# USBPROG_USBUART.net
KiCad netlist of a schematic drawn in Altium Designer
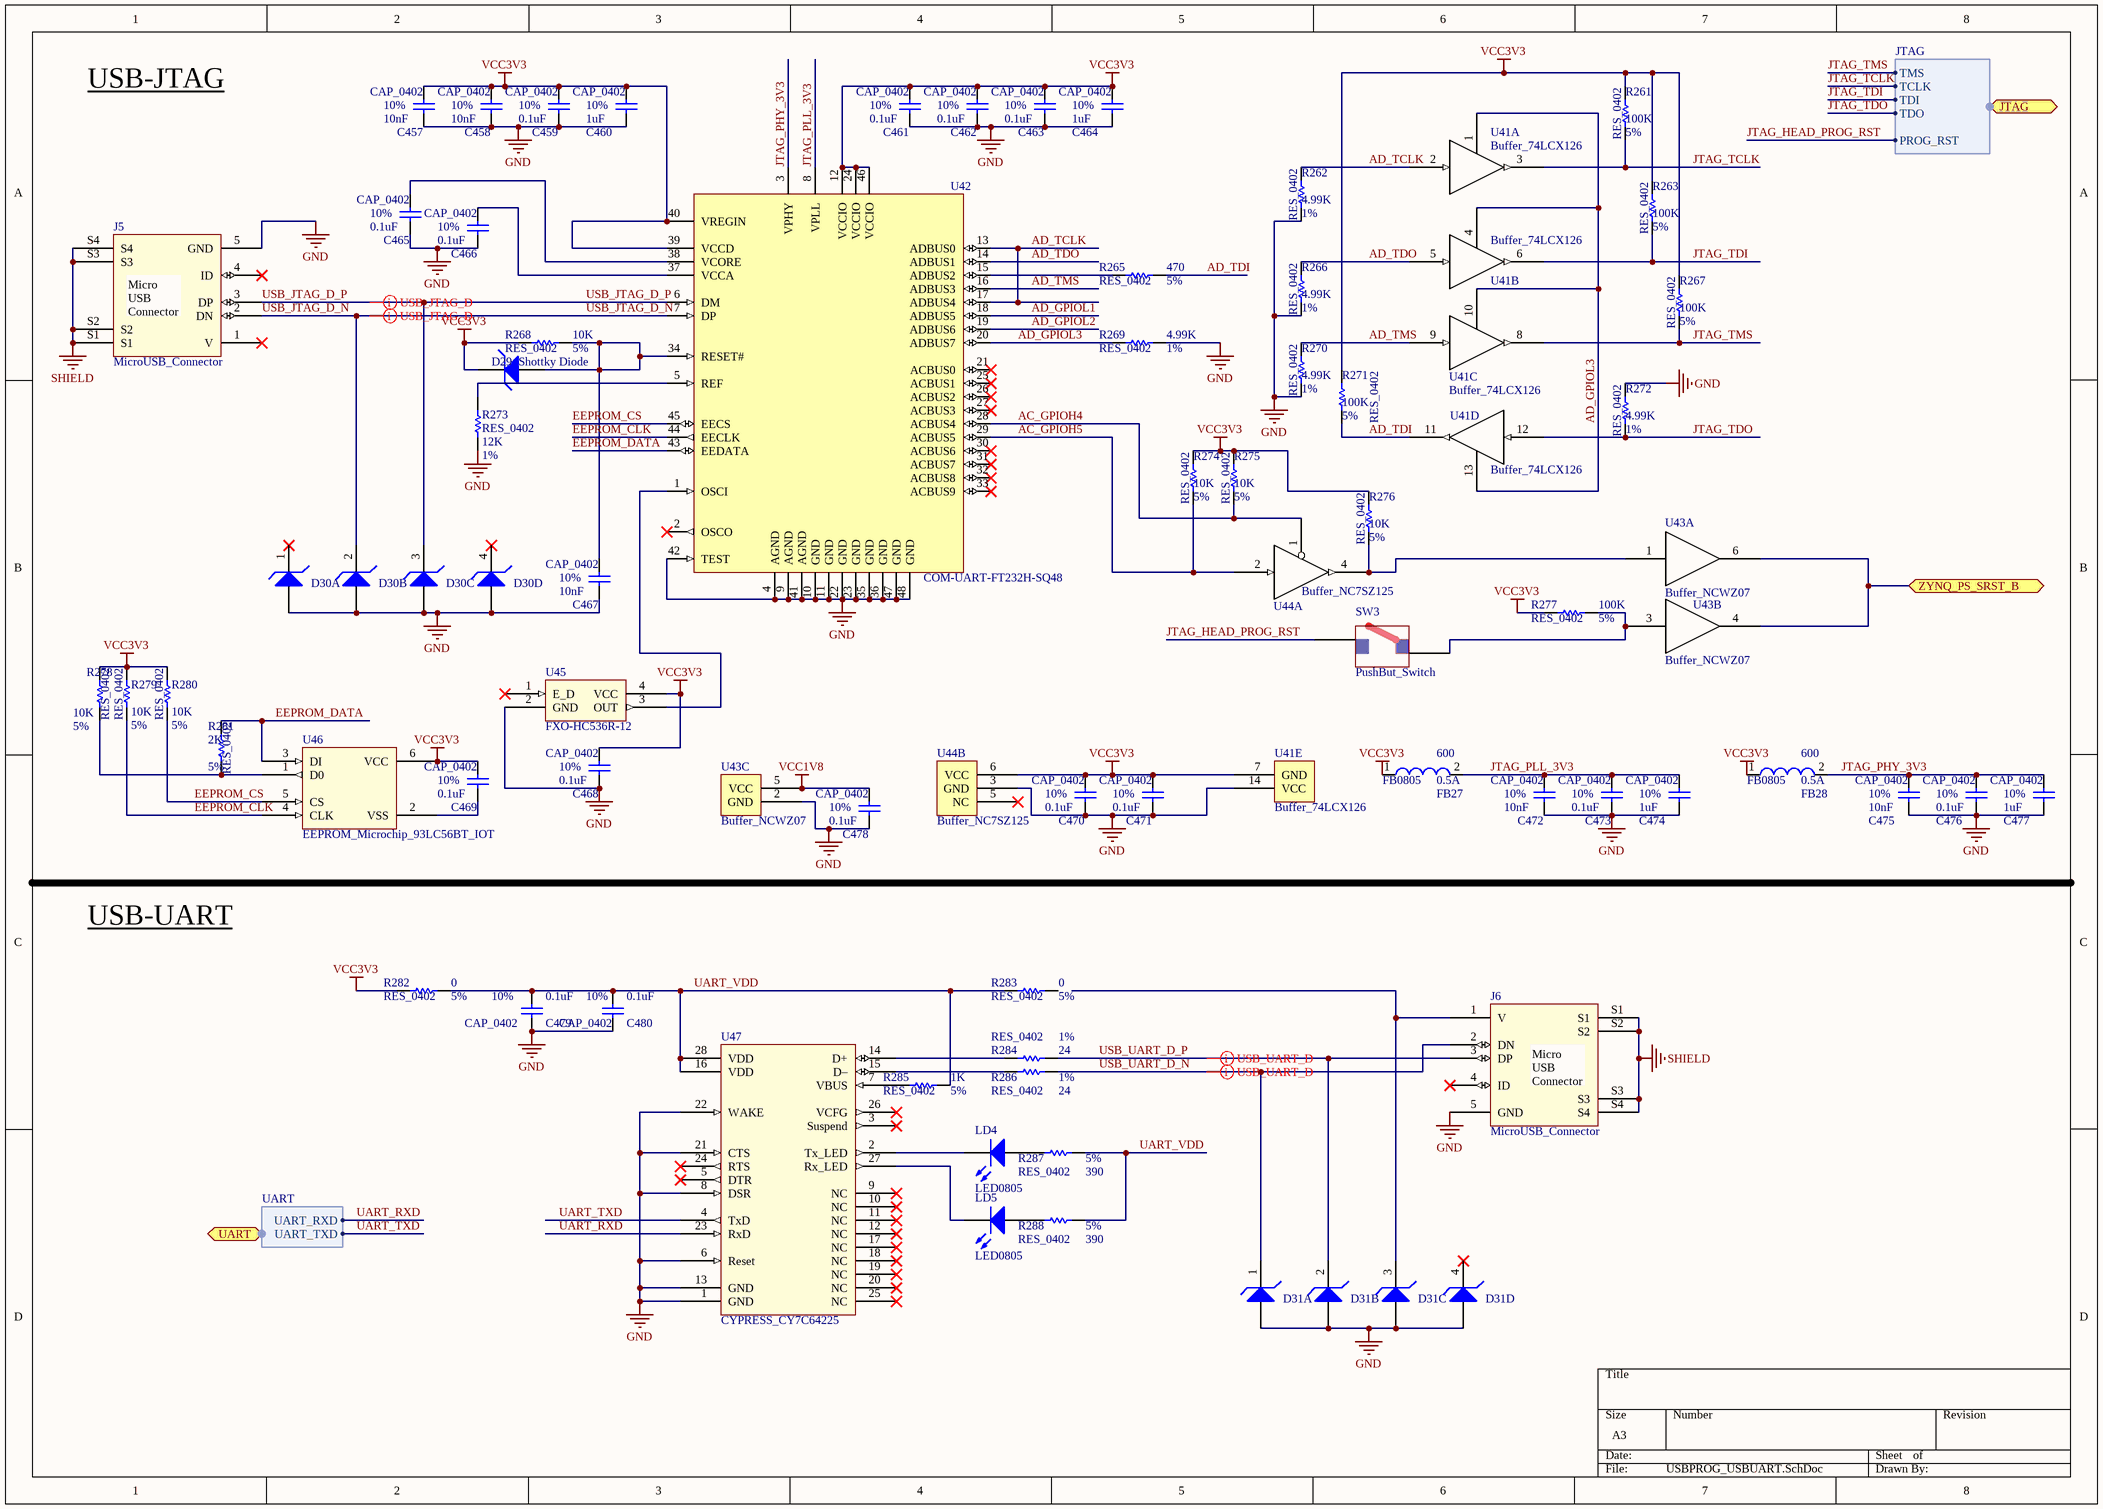
[diagram p0: USBPROG_USBUART.SchDoc]

(export (version "E")
  (design (tool "Eeschema 10.0.6"))
  (components
    (comp (ref "C457")
      (value "CAP_0402")
      (footprint "CAPC0402(1005)60_N:CAPC0402(1005)60_N")
      (description "10000pF, ceramic, 10% 6.3V X5R, 0402")
      (fields
        (field (name "ALTIUM_VALUE") "10nF")
        (field (name "TOLERANCE") "10%")
        (field (name "PART NUMBER") "GRM155R60J103KA01D")
        (field (name "MANUFACTURER") "Murata Electronics North America")
      )
      (libsource (lib "COMRAD_Database") (part "CAP_0402"))
    )
    (comp (ref "C458")
      (value "CAP_0402")
      (footprint "CAPC0402(1005)60_N:CAPC0402(1005)60_N")
      (description "10000pF, ceramic, 10% 6.3V X5R, 0402")
      (fields
        (field (name "ALTIUM_VALUE") "10nF")
        (field (name "TOLERANCE") "10%")
        (field (name "PART NUMBER") "GRM155R60J103KA01D")
        (field (name "MANUFACTURER") "Murata Electronics North America")
      )
      (libsource (lib "COMRAD_Database") (part "CAP_0402"))
    )
    (comp (ref "C459")
      (value "CAP_0402")
      (footprint "CAPC0402(1005)60_N:CAPC0402(1005)60_N")
      (description "0.1uf, ceramic, 10%, 6.3V, X5R, 0402")
      (fields
        (field (name "ALTIUM_VALUE") "0.1uF")
        (field (name "TOLERANCE") "10%")
        (field (name "PART NUMBER") "C1005X5R0J104K")
        (field (name "MANUFACTURER") "TDK Corporation")
      )
      (libsource (lib "COMRAD_Database") (part "CAP_0402"))
    )
    (comp (ref "C460")
      (value "CAP_0402")
      (footprint "CAPC0402(1005)60_N:CAPC0402(1005)60_N")
      (description "1uF, ceramic, 10%, 6.3V, X5R, 0402")
      (fields
        (field (name "ALTIUM_VALUE") "1uF")
        (field (name "TOLERANCE") "10%")
        (field (name "PART NUMBER") "C1005X5R0J105K")
        (field (name "MANUFACTURER") "TDK Corporation")
      )
      (libsource (lib "COMRAD_Database") (part "CAP_0402"))
    )
    (comp (ref "C461")
      (value "CAP_0402")
      (footprint "CAPC0402(1005)60_N:CAPC0402(1005)60_N")
      (description "0.1uf, ceramic, 10%, 6.3V, X5R, 0402")
      (fields
        (field (name "ALTIUM_VALUE") "0.1uF")
        (field (name "TOLERANCE") "10%")
        (field (name "PART NUMBER") "C1005X5R0J104K")
        (field (name "MANUFACTURER") "TDK Corporation")
      )
      (libsource (lib "COMRAD_Database") (part "CAP_0402"))
    )
    (comp (ref "C462")
      (value "CAP_0402")
      (footprint "CAPC0402(1005)60_N:CAPC0402(1005)60_N")
      (description "0.1uf, ceramic, 10%, 6.3V, X5R, 0402")
      (fields
        (field (name "ALTIUM_VALUE") "0.1uF")
        (field (name "TOLERANCE") "10%")
        (field (name "PART NUMBER") "C1005X5R0J104K")
        (field (name "MANUFACTURER") "TDK Corporation")
      )
      (libsource (lib "COMRAD_Database") (part "CAP_0402"))
    )
    (comp (ref "C463")
      (value "CAP_0402")
      (footprint "CAPC0402(1005)60_N:CAPC0402(1005)60_N")
      (description "0.1uf, ceramic, 10%, 6.3V, X5R, 0402")
      (fields
        (field (name "ALTIUM_VALUE") "0.1uF")
        (field (name "TOLERANCE") "10%")
        (field (name "PART NUMBER") "C1005X5R0J104K")
        (field (name "MANUFACTURER") "TDK Corporation")
      )
      (libsource (lib "COMRAD_Database") (part "CAP_0402"))
    )
    (comp (ref "C464")
      (value "CAP_0402")
      (footprint "CAPC0402(1005)60_N:CAPC0402(1005)60_N")
      (description "1uF, ceramic, 10%, 6.3V, X5R, 0402")
      (fields
        (field (name "ALTIUM_VALUE") "1uF")
        (field (name "TOLERANCE") "10%")
        (field (name "PART NUMBER") "C1005X5R0J105K")
        (field (name "MANUFACTURER") "TDK Corporation")
      )
      (libsource (lib "COMRAD_Database") (part "CAP_0402"))
    )
    (comp (ref "C465")
      (value "CAP_0402")
      (footprint "CAPC0402(1005)60_N:CAPC0402(1005)60_N")
      (description "0.1uf, ceramic, 10%, 6.3V, X5R, 0402")
      (fields
        (field (name "ALTIUM_VALUE") "0.1uF")
        (field (name "TOLERANCE") "10%")
        (field (name "PART NUMBER") "C1005X5R0J104K")
        (field (name "MANUFACTURER") "TDK Corporation")
      )
      (libsource (lib "COMRAD_Database") (part "CAP_0402"))
    )
    (comp (ref "C466")
      (value "CAP_0402")
      (footprint "CAPC0402(1005)60_N:CAPC0402(1005)60_N")
      (description "0.1uf, ceramic, 10%, 6.3V, X5R, 0402")
      (fields
        (field (name "ALTIUM_VALUE") "0.1uF")
        (field (name "TOLERANCE") "10%")
        (field (name "PART NUMBER") "C1005X5R0J104K")
        (field (name "MANUFACTURER") "TDK Corporation")
      )
      (libsource (lib "COMRAD_Database") (part "CAP_0402"))
    )
    (comp (ref "C467")
      (value "CAP_0402")
      (footprint "CAPC0402(1005)60_N:CAPC0402(1005)60_N")
      (description "10000pF, ceramic, 10% 6.3V X5R, 0402")
      (fields
        (field (name "ALTIUM_VALUE") "10nF")
        (field (name "TOLERANCE") "10%")
        (field (name "PART NUMBER") "GRM155R60J103KA01D")
        (field (name "MANUFACTURER") "Murata Electronics North America")
      )
      (libsource (lib "COMRAD_Database") (part "CAP_0402"))
    )
    (comp (ref "C468")
      (value "CAP_0402")
      (footprint "CAPC0402(1005)60_N:CAPC0402(1005)60_N")
      (description "0.1uf, ceramic, 10%, 6.3V, X5R, 0402")
      (fields
        (field (name "ALTIUM_VALUE") "0.1uF")
        (field (name "TOLERANCE") "10%")
        (field (name "PART NUMBER") "C1005X5R0J104K")
        (field (name "MANUFACTURER") "TDK Corporation")
      )
      (libsource (lib "COMRAD_Database") (part "CAP_0402"))
    )
    (comp (ref "C469")
      (value "CAP_0402")
      (footprint "CAPC0402(1005)60_N:CAPC0402(1005)60_N")
      (description "0.1uf, ceramic, 10%, 6.3V, X5R, 0402")
      (fields
        (field (name "ALTIUM_VALUE") "0.1uF")
        (field (name "TOLERANCE") "10%")
        (field (name "PART NUMBER") "C1005X5R0J104K")
        (field (name "MANUFACTURER") "TDK Corporation")
      )
      (libsource (lib "COMRAD_Database") (part "CAP_0402"))
    )
    (comp (ref "C470")
      (value "CAP_0402")
      (footprint "CAPC0402(1005)60_N:CAPC0402(1005)60_N")
      (description "0.1uf, ceramic, 10%, 6.3V, X5R, 0402")
      (fields
        (field (name "ALTIUM_VALUE") "0.1uF")
        (field (name "TOLERANCE") "10%")
        (field (name "PART NUMBER") "C1005X5R0J104K")
        (field (name "MANUFACTURER") "TDK Corporation")
      )
      (libsource (lib "COMRAD_Database") (part "CAP_0402"))
    )
    (comp (ref "C471")
      (value "CAP_0402")
      (footprint "CAPC0402(1005)60_N:CAPC0402(1005)60_N")
      (description "0.1uf, ceramic, 10%, 6.3V, X5R, 0402")
      (fields
        (field (name "ALTIUM_VALUE") "0.1uF")
        (field (name "TOLERANCE") "10%")
        (field (name "PART NUMBER") "C1005X5R0J104K")
        (field (name "MANUFACTURER") "TDK Corporation")
      )
      (libsource (lib "COMRAD_Database") (part "CAP_0402"))
    )
    (comp (ref "C472")
      (value "CAP_0402")
      (footprint "CAPC0402(1005)60_N:CAPC0402(1005)60_N")
      (description "10000pF, ceramic, 10% 6.3V X5R, 0402")
      (fields
        (field (name "ALTIUM_VALUE") "10nF")
        (field (name "TOLERANCE") "10%")
        (field (name "PART NUMBER") "GRM155R60J103KA01D")
        (field (name "MANUFACTURER") "Murata Electronics North America")
      )
      (libsource (lib "COMRAD_Database") (part "CAP_0402"))
    )
    (comp (ref "C473")
      (value "CAP_0402")
      (footprint "CAPC0402(1005)60_N:CAPC0402(1005)60_N")
      (description "0.1uf, ceramic, 10%, 6.3V, X5R, 0402")
      (fields
        (field (name "ALTIUM_VALUE") "0.1uF")
        (field (name "TOLERANCE") "10%")
        (field (name "PART NUMBER") "C1005X5R0J104K")
        (field (name "MANUFACTURER") "TDK Corporation")
      )
      (libsource (lib "COMRAD_Database") (part "CAP_0402"))
    )
    (comp (ref "C474")
      (value "CAP_0402")
      (footprint "CAPC0402(1005)60_N:CAPC0402(1005)60_N")
      (description "1uF, ceramic, 10%, 6.3V, X5R, 0402")
      (fields
        (field (name "ALTIUM_VALUE") "1uF")
        (field (name "TOLERANCE") "10%")
        (field (name "PART NUMBER") "C1005X5R0J105K")
        (field (name "MANUFACTURER") "TDK Corporation")
      )
      (libsource (lib "COMRAD_Database") (part "CAP_0402"))
    )
    (comp (ref "C475")
      (value "CAP_0402")
      (footprint "CAPC0402(1005)60_N:CAPC0402(1005)60_N")
      (description "10000pF, ceramic, 10% 6.3V X5R, 0402")
      (fields
        (field (name "ALTIUM_VALUE") "10nF")
        (field (name "TOLERANCE") "10%")
        (field (name "PART NUMBER") "GRM155R60J103KA01D")
        (field (name "MANUFACTURER") "Murata Electronics North America")
      )
      (libsource (lib "COMRAD_Database") (part "CAP_0402"))
    )
    (comp (ref "C476")
      (value "CAP_0402")
      (footprint "CAPC0402(1005)60_N:CAPC0402(1005)60_N")
      (description "0.1uf, ceramic, 10%, 6.3V, X5R, 0402")
      (fields
        (field (name "ALTIUM_VALUE") "0.1uF")
        (field (name "TOLERANCE") "10%")
        (field (name "PART NUMBER") "C1005X5R0J104K")
        (field (name "MANUFACTURER") "TDK Corporation")
      )
      (libsource (lib "COMRAD_Database") (part "CAP_0402"))
    )
    (comp (ref "C477")
      (value "CAP_0402")
      (footprint "CAPC0402(1005)60_N:CAPC0402(1005)60_N")
      (description "1uF, ceramic, 10%, 6.3V, X5R, 0402")
      (fields
        (field (name "ALTIUM_VALUE") "1uF")
        (field (name "TOLERANCE") "10%")
        (field (name "PART NUMBER") "C1005X5R0J105K")
        (field (name "MANUFACTURER") "TDK Corporation")
      )
      (libsource (lib "COMRAD_Database") (part "CAP_0402"))
    )
    (comp (ref "C478")
      (value "CAP_0402")
      (footprint "CAPC0402(1005)60_N:CAPC0402(1005)60_N")
      (description "0.1uf, ceramic, 10%, 6.3V, X5R, 0402")
      (fields
        (field (name "ALTIUM_VALUE") "0.1uF")
        (field (name "TOLERANCE") "10%")
        (field (name "PART NUMBER") "C1005X5R0J104K")
        (field (name "MANUFACTURER") "TDK Corporation")
      )
      (libsource (lib "COMRAD_Database") (part "CAP_0402"))
    )
    (comp (ref "C479")
      (value "CAP_0402")
      (footprint "CAPC0402(1005)60_N:CAPC0402(1005)60_N")
      (description "0.1uf, ceramic, 10%, 6.3V, X5R, 0402")
      (fields
        (field (name "ALTIUM_VALUE") "0.1uF")
        (field (name "TOLERANCE") "10%")
        (field (name "PART NUMBER") "C1005X5R0J104K")
        (field (name "MANUFACTURER") "TDK Corporation")
      )
      (libsource (lib "COMRAD_Database") (part "CAP_0402"))
    )
    (comp (ref "C480")
      (value "CAP_0402")
      (footprint "CAPC0402(1005)60_N:CAPC0402(1005)60_N")
      (description "0.1uf, ceramic, 10%, 6.3V, X5R, 0402")
      (fields
        (field (name "ALTIUM_VALUE") "0.1uF")
        (field (name "TOLERANCE") "10%")
        (field (name "PART NUMBER") "C1005X5R0J104K")
        (field (name "MANUFACTURER") "TDK Corporation")
      )
      (libsource (lib "COMRAD_Database") (part "CAP_0402"))
    )
    (comp (ref "D29")
      (value "Shottky Diode")
      (footprint "SchottkyDiode_RB751S40_2-PIN")
      (description "RB751S40, 40V 30mA schottky, SOD523F")
      (fields (field (name "PART NUMBER") "RB751S40") (field (name "MANUFACTURER") "FAIRCHILD SEMICONDUCTOR"))
      (libsource (lib "COMRAD_Database") (part "ShottkyDiode"))
    )
    (comp (ref "D30")
      (value "QuadESDDiode_TEConnectivity_SESD0802Q4UG")
      (footprint "QuadESDDiode_TEConnectivity_SESD0802Q4UG_5-PIN")
      (description "SESD0802Q4UG, Quad Diode Array for ESD protection")
      (fields (field (name "PART NUMBER") "RF2197-000") (field (name "MANUFACTURER") "TE Connectivity"))
      (libsource (lib "COMRAD_Database") (part "QuadESDDiode_TEConnectivity_SESD0802Q4UG"))
    )
    (comp (ref "D31")
      (value "QuadESDDiode_TEConnectivity_SESD0802Q4UG")
      (footprint "QuadESDDiode_TEConnectivity_SESD0802Q4UG_5-PIN")
      (description "SESD0802Q4UG, Quad Diode Array for ESD protection")
      (fields (field (name "PART NUMBER") "RF2197-000") (field (name "MANUFACTURER") "TE Connectivity"))
      (libsource (lib "COMRAD_Database") (part "QuadESDDiode_TEConnectivity_SESD0802Q4UG"))
    )
    (comp (ref "FB27")
      (value "FB0805")
      (footprint "Inductor0805(2012)")
      (description "MPZ2012S601A, 600 ohm, 100MHz, 0805")
      (fields
        (field (name "RESISTANCE") "600")
        (field (name "MAX_CURRENT") "0.5A")
        (field (name "PART NUMBER") "MPZ2012S601A")
        (field (name "MANUFACTURER") "TDK Corporation")
      )
      (libsource (lib "COMRAD_Database") (part "FerriteBead0805"))
    )
    (comp (ref "FB28")
      (value "FB0805")
      (footprint "Inductor0805(2012)")
      (description "MPZ2012S601A, 600 ohm, 100MHz, 0805")
      (fields
        (field (name "RESISTANCE") "600")
        (field (name "MAX_CURRENT") "0.5A")
        (field (name "PART NUMBER") "MPZ2012S601A")
        (field (name "MANUFACTURER") "TDK Corporation")
      )
      (libsource (lib "COMRAD_Database") (part "FerriteBead0805"))
    )
    (comp (ref "J5") (value "MicroUSB_Connector") (libsource (lib "") (part "MicroUSB_Connector_1")))
    (comp (ref "J6")
      (value "MicroUSB_Connector")
      (libsource (lib "COMRAD_Database") (part "MicroUSB_Connector"))
    )
    (comp (ref "LD4")
      (value "LED0805")
      (footprint "LED0603(1608)")
      (description "LED 565NM GRN DIFF 0603 SMD")
      (fields
        (field (name "PART NUMBER") "SML-LX0603GW-TR")
        (field (name "MANUFACTURER") "Lumex Opto/Components Inc")
      )
      (libsource (lib "COMRAD_Database") (part "LED0805"))
    )
    (comp (ref "LD5")
      (value "LED0805")
      (footprint "LED0603(1608)")
      (description "LED 565NM GRN DIFF 0603 SMD")
      (fields
        (field (name "PART NUMBER") "SML-LX0603GW-TR")
        (field (name "MANUFACTURER") "Lumex Opto/Components Inc")
      )
      (libsource (lib "COMRAD_Database") (part "LED0805"))
    )
    (comp (ref "R261")
      (value "RES_0402")
      (footprint "RESC0402(1005)_N:RESC0402(1005)_N")
      (description "100K ohm, 5%, 1/16W, 0402")
      (fields
        (field (name "ALTIUM_VALUE") "100K")
        (field (name "TOLERANCE") "5%")
        (field (name "PART NUMBER") "RC0402JR-07100KL")
        (field (name "MANUFACTURER") "Yageo America")
      )
      (libsource (lib "COMRAD_Database") (part "RES_0402"))
    )
    (comp (ref "R262")
      (value "RES_0402")
      (footprint "RESC0402(1005)_N:RESC0402(1005)_N")
      (description "4.99K ohm, 1% 1/16W, 0402")
      (fields
        (field (name "ALTIUM_VALUE") "4.99K")
        (field (name "TOLERANCE") "1%")
        (field (name "PART NUMBER") "CRCW04024K99FKED")
        (field (name "MANUFACTURER") "Vishay/Dale")
      )
      (libsource (lib "COMRAD_Database") (part "RES_0402"))
    )
    (comp (ref "R263")
      (value "RES_0402")
      (footprint "RESC0402(1005)_N:RESC0402(1005)_N")
      (description "100K ohm, 5%, 1/16W, 0402")
      (fields
        (field (name "ALTIUM_VALUE") "100K")
        (field (name "TOLERANCE") "5%")
        (field (name "PART NUMBER") "RC0402JR-07100KL")
        (field (name "MANUFACTURER") "Yageo America")
      )
      (libsource (lib "COMRAD_Database") (part "RES_0402"))
    )
    (comp (ref "R265")
      (value "RES_0402")
      (footprint "RESC0402(1005)_N:RESC0402(1005)_N")
      (description "470 ohm, 5%, 1/16W, 0402")
      (fields
        (field (name "ALTIUM_VALUE") "470")
        (field (name "TOLERANCE") "5%")
        (field (name "PART NUMBER") "MCR01MZPJ471")
        (field (name "MANUFACTURER") "ROHM")
      )
      (libsource (lib "COMRAD_Database") (part "RES_0402"))
    )
    (comp (ref "R266")
      (value "RES_0402")
      (footprint "RESC0402(1005)_N:RESC0402(1005)_N")
      (description "4.99K ohm, 1% 1/16W, 0402")
      (fields
        (field (name "ALTIUM_VALUE") "4.99K")
        (field (name "TOLERANCE") "1%")
        (field (name "PART NUMBER") "CRCW04024K99FKED")
        (field (name "MANUFACTURER") "Vishay/Dale")
      )
      (libsource (lib "COMRAD_Database") (part "RES_0402"))
    )
    (comp (ref "R267")
      (value "RES_0402")
      (footprint "RESC0402(1005)_N:RESC0402(1005)_N")
      (description "100K ohm, 5%, 1/16W, 0402")
      (fields
        (field (name "ALTIUM_VALUE") "100K")
        (field (name "TOLERANCE") "5%")
        (field (name "PART NUMBER") "RC0402JR-07100KL")
        (field (name "MANUFACTURER") "Yageo America")
      )
      (libsource (lib "COMRAD_Database") (part "RES_0402"))
    )
    (comp (ref "R268")
      (value "RES_0402")
      (footprint "RESC0402(1005)_N:RESC0402(1005)_N")
      (description "10K ohm, 5%, 1/16W, 0402")
      (fields
        (field (name "ALTIUM_VALUE") "10K")
        (field (name "TOLERANCE") "5%")
        (field (name "PART NUMBER") "RC0402JR-0710KL")
        (field (name "MANUFACTURER") "Yageo America")
      )
      (libsource (lib "COMRAD_Database") (part "RES_0402"))
    )
    (comp (ref "R269")
      (value "RES_0402")
      (footprint "RESC0402(1005)_N:RESC0402(1005)_N")
      (description "4.99K ohm, 1% 1/16W, 0402")
      (fields
        (field (name "ALTIUM_VALUE") "4.99K")
        (field (name "TOLERANCE") "1%")
        (field (name "PART NUMBER") "CRCW04024K99FKED")
        (field (name "MANUFACTURER") "Vishay/Dale")
      )
      (libsource (lib "COMRAD_Database") (part "RES_0402"))
    )
    (comp (ref "R270")
      (value "RES_0402")
      (footprint "RESC0402(1005)_N:RESC0402(1005)_N")
      (description "4.99K ohm, 1% 1/16W, 0402")
      (fields
        (field (name "ALTIUM_VALUE") "4.99K")
        (field (name "TOLERANCE") "1%")
        (field (name "PART NUMBER") "CRCW04024K99FKED")
        (field (name "MANUFACTURER") "Vishay/Dale")
      )
      (libsource (lib "COMRAD_Database") (part "RES_0402"))
    )
    (comp (ref "R271")
      (value "RES_0402")
      (footprint "RESC0402(1005)_N:RESC0402(1005)_N")
      (description "100K ohm, 5%, 1/16W, 0402")
      (fields
        (field (name "ALTIUM_VALUE") "100K")
        (field (name "TOLERANCE") "5%")
        (field (name "PART NUMBER") "RC0402JR-07100KL")
        (field (name "MANUFACTURER") "Yageo America")
      )
      (libsource (lib "COMRAD_Database") (part "RES_0402"))
    )
    (comp (ref "R272")
      (value "RES_0402")
      (footprint "RESC0402(1005)_N:RESC0402(1005)_N")
      (description "4.99K ohm, 1% 1/16W, 0402")
      (fields
        (field (name "ALTIUM_VALUE") "4.99K")
        (field (name "TOLERANCE") "1%")
        (field (name "PART NUMBER") "CRCW04024K99FKED")
        (field (name "MANUFACTURER") "Vishay/Dale")
      )
      (libsource (lib "COMRAD_Database") (part "RES_0402"))
    )
    (comp (ref "R273")
      (value "RES_0402")
      (footprint "RESC0402(1005)_N:RESC0402(1005)_N")
      (description "12K ohm, 1% 1/10W, 0402")
      (fields
        (field (name "ALTIUM_VALUE") "12K")
        (field (name "TOLERANCE") "1%")
        (field (name "PART NUMBER") "ERJ-2RKF1202X")
        (field (name "MANUFACTURER") "Panasonic - ECG")
      )
      (libsource (lib "COMRAD_Database") (part "RES_0402"))
    )
    (comp (ref "R274")
      (value "RES_0402")
      (footprint "RESC0402(1005)_N:RESC0402(1005)_N")
      (description "10K ohm, 5%, 1/16W, 0402")
      (fields
        (field (name "ALTIUM_VALUE") "10K")
        (field (name "TOLERANCE") "5%")
        (field (name "PART NUMBER") "RC0402JR-0710KL")
        (field (name "MANUFACTURER") "Yageo America")
      )
      (libsource (lib "COMRAD_Database") (part "RES_0402"))
    )
    (comp (ref "R275")
      (value "RES_0402")
      (footprint "RESC0402(1005)_N:RESC0402(1005)_N")
      (description "10K ohm, 5%, 1/16W, 0402")
      (fields
        (field (name "ALTIUM_VALUE") "10K")
        (field (name "TOLERANCE") "5%")
        (field (name "PART NUMBER") "RC0402JR-0710KL")
        (field (name "MANUFACTURER") "Yageo America")
      )
      (libsource (lib "COMRAD_Database") (part "RES_0402"))
    )
    (comp (ref "R276")
      (value "RES_0402")
      (footprint "RESC0402(1005)_N:RESC0402(1005)_N")
      (description "10K ohm, 5%, 1/16W, 0402")
      (fields
        (field (name "ALTIUM_VALUE") "10K")
        (field (name "TOLERANCE") "5%")
        (field (name "PART NUMBER") "RC0402JR-0710KL")
        (field (name "MANUFACTURER") "Yageo America")
      )
      (libsource (lib "COMRAD_Database") (part "RES_0402"))
    )
    (comp (ref "R277")
      (value "RES_0402")
      (footprint "RESC0402(1005)_N:RESC0402(1005)_N")
      (description "100K ohm, 5%, 1/16W, 0402")
      (fields
        (field (name "ALTIUM_VALUE") "100K")
        (field (name "TOLERANCE") "5%")
        (field (name "PART NUMBER") "RC0402JR-07100KL")
        (field (name "MANUFACTURER") "Yageo America")
      )
      (libsource (lib "COMRAD_Database") (part "RES_0402"))
    )
    (comp (ref "R278")
      (value "RES_0402")
      (footprint "RESC0402(1005)_N:RESC0402(1005)_N")
      (description "10K ohm, 5%, 1/16W, 0402")
      (fields
        (field (name "ALTIUM_VALUE") "10K")
        (field (name "TOLERANCE") "5%")
        (field (name "PART NUMBER") "RC0402JR-0710KL")
        (field (name "MANUFACTURER") "Yageo America")
      )
      (libsource (lib "COMRAD_Database") (part "RES_0402"))
    )
    (comp (ref "R279")
      (value "RES_0402")
      (footprint "RESC0402(1005)_N:RESC0402(1005)_N")
      (description "10K ohm, 5%, 1/16W, 0402")
      (fields
        (field (name "ALTIUM_VALUE") "10K")
        (field (name "TOLERANCE") "5%")
        (field (name "PART NUMBER") "RC0402JR-0710KL")
        (field (name "MANUFACTURER") "Yageo America")
      )
      (libsource (lib "COMRAD_Database") (part "RES_0402"))
    )
    (comp (ref "R280")
      (value "RES_0402")
      (footprint "RESC0402(1005)_N:RESC0402(1005)_N")
      (description "10K ohm, 5%, 1/16W, 0402")
      (fields
        (field (name "ALTIUM_VALUE") "10K")
        (field (name "TOLERANCE") "5%")
        (field (name "PART NUMBER") "RC0402JR-0710KL")
        (field (name "MANUFACTURER") "Yageo America")
      )
      (libsource (lib "COMRAD_Database") (part "RES_0402"))
    )
    (comp (ref "R281")
      (value "RES_0402")
      (footprint "RESC0402(1005)_N:RESC0402(1005)_N")
      (description "2K ohm, 5% 1/16W, 0402")
      (fields
        (field (name "ALTIUM_VALUE") "2K")
        (field (name "TOLERANCE") "5%")
        (field (name "PART NUMBER") "ERJ-2GEJ202X")
        (field (name "MANUFACTURER") "Panasonic - ECG")
      )
      (libsource (lib "COMRAD_Database") (part "RES_0402"))
    )
    (comp (ref "R282")
      (value "RES_0402")
      (footprint "RESC0402(1005)_N")
      (description "0.0 ohm shunt, 5%, 1/16W, 0402")
      (fields
        (field (name "ALTIUM_VALUE") "0")
        (field (name "TOLERANCE") "5%")
        (field (name "PART NUMBER") "RC0402JR-070RL")
        (field (name "MANUFACTURER") "Yageo America")
      )
      (libsource (lib "COMRAD_Database") (part "RES_0805"))
    )
    (comp (ref "R283")
      (value "RES_0402")
      (footprint "RESC0402(1005)_N")
      (description "0.0 ohm shunt, 5%, 1/16W, 0402")
      (fields
        (field (name "ALTIUM_VALUE") "0")
        (field (name "TOLERANCE") "5%")
        (field (name "PART NUMBER") "RC0402JR-070RL")
        (field (name "MANUFACTURER") "Yageo America")
      )
      (libsource (lib "COMRAD_Database") (part "RES_0805"))
    )
    (comp (ref "R284")
      (value "RES_0402")
      (footprint "RESC0402(1005)_N:RESC0402(1005)_N")
      (description "24 ohm, 1% 1/16W, 0402")
      (fields
        (field (name "ALTIUM_VALUE") "24")
        (field (name "TOLERANCE") "1%")
        (field (name "PART NUMBER") "CRCW040224R0FKED")
        (field (name "MANUFACTURER") "Vishay/Dale")
      )
      (libsource (lib "COMRAD_Database") (part "RES_0402"))
    )
    (comp (ref "R285")
      (value "RES_0402")
      (footprint "RESC0402(1005)_N:RESC0402(1005)_N")
      (description "1K ohm, 5%, 1/16W, 0402")
      (fields
        (field (name "ALTIUM_VALUE") "1K")
        (field (name "TOLERANCE") "5%")
        (field (name "PART NUMBER") "RC0402JR-071KL")
        (field (name "MANUFACTURER") "Yageo America")
      )
      (libsource (lib "COMRAD_Database") (part "RES_0402"))
    )
    (comp (ref "R286")
      (value "RES_0402")
      (footprint "RESC0402(1005)_N:RESC0402(1005)_N")
      (description "24 ohm, 1% 1/16W, 0402")
      (fields
        (field (name "ALTIUM_VALUE") "24")
        (field (name "TOLERANCE") "1%")
        (field (name "PART NUMBER") "CRCW040224R0FKED")
        (field (name "MANUFACTURER") "Vishay/Dale")
      )
      (libsource (lib "COMRAD_Database") (part "RES_0402"))
    )
    (comp (ref "R287")
      (value "RES_0402")
      (footprint "RESC0402(1005)_N:RESC0402(1005)_N")
      (description "390 ohm, 5%, 1/16W, 0402")
      (fields
        (field (name "ALTIUM_VALUE") "390")
        (field (name "TOLERANCE") "5%")
        (field (name "PART NUMBER") "RC0402JR-07390RL")
        (field (name "MANUFACTURER") "Yageo America")
      )
      (libsource (lib "COMRAD_Database") (part "RES_0402"))
    )
    (comp (ref "R288")
      (value "RES_0402")
      (footprint "RESC0402(1005)_N:RESC0402(1005)_N")
      (description "390 ohm, 5%, 1/16W, 0402")
      (fields
        (field (name "ALTIUM_VALUE") "390")
        (field (name "TOLERANCE") "5%")
        (field (name "PART NUMBER") "RC0402JR-07390RL")
        (field (name "MANUFACTURER") "Yageo America")
      )
      (libsource (lib "COMRAD_Database") (part "RES_0402"))
    )
    (comp (ref "SW3")
      (value "PushBut_Switch")
      (footprint "PushButtonSwitch_CnK_1.14002.1110000")
      (description "SWITCH PUSH SPST-NO 0.1A 35V")
      (fields (field (name "PART NUMBER") "1.14002.1110000") (field (name "MANUFACTURER") "C&K Components"))
      (libsource (lib "COMRAD_Database") (part "PushBut_Switch"))
    )
    (comp (ref "U41")
      (value "Buffer_74LCX126")
      (footprint "Buffer_Fairchild_74LCX126_DQFN-14")
      (description "74LCX126BQX, quad buffer, LV N-Inv, DQFN14")
      (fields
        (field (name "PART NUMBER") "74LCX126BQX")
        (field (name "MANUFACTURER") "FAIRCHILD SEMICONDUCTOR")
      )
      (libsource (lib "COMRAD_Database") (part "Buffer_74LCX126"))
    )
    (comp (ref "U42")
      (value "COM-UART-FT232H-SQ48")
      (footprint "USB_COM_FTDI_FT232HQTRAY_QFN48_N")
      (description "FT232HQ, USB HS to UART/FIFO SPI/JTAG/I2C, QFN-48")
      (fields (field (name "PART NUMBER") "FT232HQ") (field (name "MANUFACTURER") "FTDI"))
      (libsource (lib "COMRAD_Database") (part "COM-UART-FT232H-SQ48"))
    )
    (comp (ref "U43")
      (value "Buffer_NCWZ07")
      (footprint "Buffer_Fairchild_NCWZ07_SC70-6")
      (description "NC7WZ07, dual non-inverting buffer, SC-70-6 (SOT-363)")
      (fields
        (field (name "PART NUMBER") "NC7WZ07P6X")
        (field (name "MANUFACTURER") "FAIRCHILD OPTOELECTRICS GROUP")
      )
      (libsource (lib "COMRAD_Database") (part "Buffer_Fairchild_NCWZ07"))
    )
    (comp (ref "U44")
      (value "Buffer_NC7SZ125")
      (footprint "Buffer_Fairchild_NC7SZ125_SOT95P280X145-5N")
      (description "NC7SZ125M5X, Tri-State Buffer UHS, SOT-23")
      (fields
        (field (name "PART NUMBER") "NC7SZ125M5X")
        (field (name "MANUFACTURER") "FAIRCHILD SEMICONDUCTOR")
      )
      (libsource (lib "COMRAD_Database") (part "Buffer_NC7SZ125"))
    )
    (comp (ref "U45")
      (value "FXO-HC536R-12")
      (footprint "Oscillator_Fox_767-12-69_HC5")
      (description "767-12-69, 12MHz 3.3V HCMOS Oscillator, HC5")
      (fields (field (name "MANUFACTURER") "Fox Electronics"))
      (libsource (lib "COMRAD_Database") (part "Oscillator_Fox_767-12-69"))
    )
    (comp (ref "U46")
      (value "EEPROM_Microchip_93LC56BT_IOT")
      (footprint "EEPROM_Microchip_93LC56BT_IOT_SOT23-6")
      (description "93LC56BT-I/OT, EEPROM 2Kbit 3MHz, SOT23-6")
      (fields
        (field (name "PART NUMBER") "93LC56BT-I/OT")
        (field (name "MANUFACTURER") "Microchip Technology")
      )
      (libsource (lib "COMRAD_Database") (part "EEPROM_Microchip_93LC56BT_IOT"))
    )
    (comp (ref "U47")
      (value "CYPRESS_CY7C64225")
      (footprint "Cypress_USB_UART_CY7C64225_SSSOP28")
      (description "CY7C64225-28PVXC, USB-UART bridge")
      (fields
        (field (name "PART NUMBER") "CY7C64225-28PVXC")
        (field (name "MANUFACTURER") "Cypress Semiconductor")
      )
      (libsource (lib "COMRAD_Database") (part "CYPRESS_CY7C64225"))
    )
  )
  (nets
    (net (code "3") (name "/AC_GPIOH4") (class "Default")
      (node (ref "R275") (pin "1") (pinfunction "1_1") (pintype "passive"))
      (node (ref "U42") (pin "28") (pinfunction "ACBUS4_28") (pintype "bidirectional"))
      (node (ref "U44") (pin "1") (pintype "passive"))
    )
    (net (code "4") (name "/AC_GPIOH5") (class "Default")
      (node (ref "R274") (pin "1") (pinfunction "1_1") (pintype "passive"))
      (node (ref "U42") (pin "29") (pinfunction "ACBUS5_29") (pintype "bidirectional"))
      (node (ref "U44") (pin "2") (pintype "input"))
    )
    (net (code "5") (name "/AD_GPIOL1") (class "Default")
      (node (ref "U42") (pin "18") (pinfunction "ADBUS5_18") (pintype "bidirectional"))
    )
    (net (code "6") (name "/AD_GPIOL2") (class "Default")
      (node (ref "U42") (pin "19") (pinfunction "ADBUS6_19") (pintype "bidirectional"))
    )
    (net (code "7") (name "/AD_GPIOL3") (class "Default")
      (node (ref "R269") (pin "1") (pinfunction "1_1") (pintype "passive"))
      (node (ref "U41") (pin "1") (pintype "passive"))
      (node (ref "U41") (pin "10") (pintype "passive"))
      (node (ref "U41") (pin "13") (pintype "passive"))
      (node (ref "U41") (pin "4") (pintype "passive"))
      (node (ref "U42") (pin "20") (pinfunction "ADBUS7_20") (pintype "bidirectional"))
    )
    (net (code "8") (name "/AD_TCLK") (class "Default")
      (node (ref "R262") (pin "2") (pinfunction "2_2") (pintype "passive"))
      (node (ref "U41") (pin "2") (pintype "input"))
      (node (ref "U42") (pin "13") (pinfunction "ADBUS0_13") (pintype "bidirectional"))
      (node (ref "U42") (pin "17") (pinfunction "ADBUS4_17") (pintype "bidirectional"))
    )
    (net (code "9") (name "/AD_TDI") (class "Default")
      (node (ref "R265") (pin "2") (pinfunction "2_2") (pintype "passive"))
      (node (ref "R271") (pin "1") (pinfunction "1_1") (pintype "passive"))
      (node (ref "U41") (pin "11") (pintype "output"))
    )
    (net (code "10") (name "/AD_TDO") (class "Default")
      (node (ref "R266") (pin "2") (pinfunction "2_2") (pintype "passive"))
      (node (ref "U41") (pin "5") (pintype "input"))
      (node (ref "U42") (pin "14") (pinfunction "ADBUS1_14") (pintype "bidirectional"))
    )
    (net (code "11") (name "/AD_TMS") (class "Default")
      (node (ref "R270") (pin "2") (pinfunction "2_2") (pintype "passive"))
      (node (ref "U41") (pin "9") (pintype "input"))
      (node (ref "U42") (pin "16") (pinfunction "ADBUS3_16") (pintype "bidirectional"))
    )
    (net (code "12") (name "/EEPROM_CLK") (class "Default")
      (node (ref "R279") (pin "1") (pinfunction "1_1") (pintype "passive"))
      (node (ref "U42") (pin "44") (pinfunction "EECLK_44") (pintype "output"))
      (node (ref "U46") (pin "4") (pinfunction "CLK_4") (pintype "input"))
    )
    (net (code "13") (name "/EEPROM_CS") (class "Default")
      (node (ref "R280") (pin "1") (pinfunction "1_1") (pintype "passive"))
      (node (ref "U42") (pin "45") (pinfunction "EECS_45") (pintype "bidirectional"))
      (node (ref "U46") (pin "5") (pinfunction "CS_5") (pintype "input"))
    )
    (net (code "14") (name "/EEPROM_DATA") (class "Default")
      (node (ref "R281") (pin "2") (pinfunction "2_2") (pintype "passive"))
      (node (ref "U42") (pin "43") (pinfunction "EEDATA_43") (pintype "bidirectional"))
      (node (ref "U46") (pin "3") (pinfunction "DI_3") (pintype "input"))
    )
    (net (code "15") (name "/JTAG_HEAD_PROG_RST") (class "Default")
      (node (ref "SW3") (pin "3") (pintype "passive"))
    )
    (net (code "16") (name "/JTAG_PHY_3V3") (class "Default")
      (node (ref "C475") (pin "2") (pinfunction "2_2") (pintype "passive"))
      (node (ref "C476") (pin "2") (pinfunction "2_2") (pintype "passive"))
      (node (ref "C477") (pin "2") (pinfunction "2_2") (pintype "passive"))
      (node (ref "FB28") (pin "2") (pinfunction "2_2") (pintype "passive"))
      (node (ref "U42") (pin "3") (pinfunction "VPHY_3") (pintype "power_in"))
    )
    (net (code "17") (name "/JTAG_PLL_3V3") (class "Default")
      (node (ref "C472") (pin "2") (pinfunction "2_2") (pintype "passive"))
      (node (ref "C473") (pin "2") (pinfunction "2_2") (pintype "passive"))
      (node (ref "C474") (pin "2") (pinfunction "2_2") (pintype "passive"))
      (node (ref "FB27") (pin "2") (pinfunction "2_2") (pintype "passive"))
      (node (ref "U42") (pin "8") (pinfunction "VPLL_8") (pintype "power_in"))
    )
    (net (code "18") (name "/JTAG_TCLK") (class "Default")
      (node (ref "R261") (pin "1") (pinfunction "1_1") (pintype "passive"))
      (node (ref "U41") (pin "3") (pintype "output"))
    )
    (net (code "19") (name "/JTAG_TDI") (class "Default")
      (node (ref "R263") (pin "1") (pinfunction "1_1") (pintype "passive"))
      (node (ref "U41") (pin "6") (pintype "output"))
    )
    (net (code "20") (name "/JTAG_TDO") (class "Default")
      (node (ref "R272") (pin "1") (pinfunction "1_1") (pintype "passive"))
      (node (ref "U41") (pin "12") (pintype "input"))
    )
    (net (code "21") (name "/JTAG_TMS") (class "Default")
      (node (ref "R267") (pin "1") (pinfunction "1_1") (pintype "passive"))
      (node (ref "U41") (pin "8") (pintype "output"))
    )
    (net (code "22") (name "/UART_RXD") (class "Default")
      (node (ref "U47") (pin "23") (pinfunction "RxD_23") (pintype "input"))
    )
    (net (code "23") (name "/UART_TXD") (class "Default")
      (node (ref "U47") (pin "4") (pinfunction "TxD_4") (pintype "output"))
    )
    (net (code "24") (name "/UART_VDD") (class "Default")
      (node (ref "C479") (pin "1") (pinfunction "1_1") (pintype "passive"))
      (node (ref "C480") (pin "1") (pinfunction "1_1") (pintype "passive"))
      (node (ref "R282") (pin "2") (pinfunction "2_2") (pintype "passive"))
      (node (ref "R283") (pin "1") (pinfunction "1_1") (pintype "passive"))
      (node (ref "R285") (pin "2") (pinfunction "2_2") (pintype "passive"))
      (node (ref "R287") (pin "2") (pinfunction "2_2") (pintype "passive"))
      (node (ref "R288") (pin "2") (pinfunction "2_2") (pintype "passive"))
      (node (ref "U47") (pin "16") (pinfunction "VDD_16") (pintype "power_in"))
      (node (ref "U47") (pin "28") (pinfunction "VDD_28") (pintype "power_in"))
    )
    (net (code "25") (name "/USB_JTAG_D_N") (class "Default")
      (node (ref "D30") (pin "2") (pinfunction "K_2") (pintype "passive"))
      (node (ref "J5") (pin "2") (pinfunction "DN_2") (pintype "bidirectional"))
      (node (ref "U42") (pin "7") (pinfunction "DP_7") (pintype "input"))
    )
    (net (code "26") (name "/USB_JTAG_D_P") (class "Default")
      (node (ref "D30") (pin "3") (pinfunction "K_3") (pintype "passive"))
      (node (ref "J5") (pin "3") (pinfunction "DP_3") (pintype "bidirectional"))
      (node (ref "U42") (pin "6") (pinfunction "DM_6") (pintype "input"))
    )
    (net (code "27") (name "/USB_UART_D_N") (class "Default")
      (node (ref "D31") (pin "1") (pinfunction "K_1") (pintype "passive"))
      (node (ref "J6") (pin "2") (pinfunction "DN_2") (pintype "bidirectional"))
      (node (ref "R286") (pin "2") (pinfunction "2_2") (pintype "passive"))
    )
    (net (code "28") (name "/USB_UART_D_P") (class "Default")
      (node (ref "D31") (pin "2") (pinfunction "K_2") (pintype "passive"))
      (node (ref "J6") (pin "3") (pinfunction "DP_3") (pintype "bidirectional"))
      (node (ref "R284") (pin "2") (pinfunction "2_2") (pintype "passive"))
    )
    (net (code "29") (name "/ZYNQ_PS_SRST_B") (class "Default")
      (node (ref "U43") (pin "4") (pintype "passive"))
      (node (ref "U43") (pin "6") (pintype "passive"))
    )
    (net (code "32") (name "GND") (class "Default")
      (node (ref "C457") (pin "1") (pinfunction "1_1") (pintype "passive"))
      (node (ref "C458") (pin "1") (pinfunction "1_1") (pintype "passive"))
      (node (ref "C459") (pin "1") (pinfunction "1_1") (pintype "passive"))
      (node (ref "C460") (pin "1") (pinfunction "1_1") (pintype "passive"))
      (node (ref "C461") (pin "1") (pinfunction "1_1") (pintype "passive"))
      (node (ref "C462") (pin "1") (pinfunction "1_1") (pintype "passive"))
      (node (ref "C463") (pin "1") (pinfunction "1_1") (pintype "passive"))
      (node (ref "C464") (pin "1") (pinfunction "1_1") (pintype "passive"))
      (node (ref "C465") (pin "1") (pinfunction "1_1") (pintype "passive"))
      (node (ref "C466") (pin "1") (pinfunction "1_1") (pintype "passive"))
      (node (ref "C467") (pin "1") (pinfunction "1_1") (pintype "passive"))
      (node (ref "C468") (pin "1") (pinfunction "1_1") (pintype "passive"))
      (node (ref "C470") (pin "1") (pinfunction "1_1") (pintype "passive"))
      (node (ref "C471") (pin "1") (pinfunction "1_1") (pintype "passive"))
      (node (ref "C472") (pin "1") (pinfunction "1_1") (pintype "passive"))
      (node (ref "C473") (pin "1") (pinfunction "1_1") (pintype "passive"))
      (node (ref "C474") (pin "1") (pinfunction "1_1") (pintype "passive"))
      (node (ref "C475") (pin "1") (pinfunction "1_1") (pintype "passive"))
      (node (ref "C476") (pin "1") (pinfunction "1_1") (pintype "passive"))
      (node (ref "C477") (pin "1") (pinfunction "1_1") (pintype "passive"))
      (node (ref "C478") (pin "1") (pinfunction "1_1") (pintype "passive"))
      (node (ref "C479") (pin "2") (pinfunction "2_2") (pintype "passive"))
      (node (ref "C480") (pin "2") (pinfunction "2_2") (pintype "passive"))
      (node (ref "D30") (pin "G") (pinfunction "A_G") (pintype "passive"))
      (node (ref "D31") (pin "G") (pinfunction "A_G") (pintype "passive"))
      (node (ref "J5") (pin "5") (pinfunction "GND_5") (pintype "power_in"))
      (node (ref "J6") (pin "5") (pinfunction "GND_5") (pintype "power_in"))
      (node (ref "R262") (pin "1") (pinfunction "1_1") (pintype "passive"))
      (node (ref "R266") (pin "1") (pinfunction "1_1") (pintype "passive"))
      (node (ref "R269") (pin "2") (pinfunction "2_2") (pintype "passive"))
      (node (ref "R270") (pin "1") (pinfunction "1_1") (pintype "passive"))
      (node (ref "R272") (pin "2") (pinfunction "2_2") (pintype "passive"))
      (node (ref "R273") (pin "1") (pinfunction "1_1") (pintype "passive"))
      (node (ref "U41") (pin "14") (pinfunction "VCC_14") (pintype "passive"))
      (node (ref "U42") (pin "10") (pinfunction "GND_10") (pintype "power_in"))
      (node (ref "U42") (pin "11") (pinfunction "GND_11") (pintype "power_in"))
      (node (ref "U42") (pin "22") (pinfunction "GND_22") (pintype "power_in"))
      (node (ref "U42") (pin "23") (pinfunction "GND_23") (pintype "power_in"))
      (node (ref "U42") (pin "35") (pinfunction "GND_35") (pintype "power_in"))
      (node (ref "U42") (pin "36") (pinfunction "GND_36") (pintype "power_in"))
      (node (ref "U42") (pin "4") (pinfunction "AGND_4") (pintype "power_in"))
      (node (ref "U42") (pin "41") (pinfunction "AGND_41") (pintype "power_in"))
      (node (ref "U42") (pin "42") (pinfunction "TEST_42") (pintype "input"))
      (node (ref "U42") (pin "47") (pinfunction "GND_47") (pintype "power_in"))
      (node (ref "U42") (pin "48") (pinfunction "GND_48") (pintype "power_in"))
      (node (ref "U42") (pin "9") (pinfunction "AGND_9") (pintype "power_in"))
      (node (ref "U43") (pin "2") (pinfunction "GND_2") (pintype "passive"))
      (node (ref "U44") (pin "3") (pinfunction "GND_3") (pintype "passive"))
      (node (ref "U45") (pin "2") (pinfunction "GND_2") (pintype "power_in"))
      (node (ref "U47") (pin "1") (pinfunction "GND_1") (pintype "power_in"))
      (node (ref "U47") (pin "13") (pinfunction "GND_13") (pintype "power_in"))
      (node (ref "U47") (pin "21") (pinfunction "CTS_21") (pintype "input"))
      (node (ref "U47") (pin "22") (pinfunction "WAKE_22") (pintype "input"))
      (node (ref "U47") (pin "6") (pinfunction "Reset_6") (pintype "input"))
      (node (ref "U47") (pin "8") (pinfunction "DSR_8") (pintype "input"))
    )
    (net (code "33") (name "Net-(D29-A)") (class "Default")
      (node (ref "C467") (pin "2") (pinfunction "2_2") (pintype "passive"))
      (node (ref "D29") (pin "2") (pinfunction "A_2") (pintype "passive"))
      (node (ref "R268") (pin "2") (pinfunction "2_2") (pintype "passive"))
      (node (ref "U42") (pin "34") (pinfunction "RESET#_34") (pintype "input"))
    )
    (net (code "34") (name "Net-(D31C-K)") (class "Default")
      (node (ref "D31") (pin "3") (pinfunction "K_3") (pintype "passive"))
      (node (ref "J6") (pin "1") (pinfunction "V_1") (pintype "power_in"))
    )
    (net (code "35") (name "Net-(LD4-A)") (class "Default")
      (node (ref "LD4") (pin "2") (pinfunction "A_2") (pintype "passive"))
      (node (ref "R287") (pin "1") (pinfunction "1_1") (pintype "passive"))
    )
    (net (code "36") (name "Net-(LD4-K)") (class "Default")
      (node (ref "LD4") (pin "1") (pinfunction "K_1") (pintype "passive"))
      (node (ref "U47") (pin "2") (pinfunction "Tx_LED_2") (pintype "output"))
    )
    (net (code "37") (name "Net-(LD5-A)") (class "Default")
      (node (ref "LD5") (pin "2") (pinfunction "A_2") (pintype "passive"))
      (node (ref "R288") (pin "1") (pinfunction "1_1") (pintype "passive"))
    )
    (net (code "38") (name "Net-(LD5-K)") (class "Default")
      (node (ref "LD5") (pin "1") (pinfunction "K_1") (pintype "passive"))
      (node (ref "U47") (pin "27") (pinfunction "Rx_LED_27") (pintype "output"))
    )
    (net (code "39") (name "Net-(R276-Pad1)") (class "Default")
      (node (ref "R276") (pin "1") (pinfunction "1_1") (pintype "passive"))
      (node (ref "U43") (pin "1") (pintype "passive"))
      (node (ref "U44") (pin "4") (pintype "output"))
    )
    (net (code "40") (name "Net-(R277-Pad1)") (class "Default")
      (node (ref "R277") (pin "1") (pinfunction "1_1") (pintype "passive"))
      (node (ref "SW3") (pin "4") (pintype "passive"))
      (node (ref "U43") (pin "3") (pintype "passive"))
    )
    (net (code "41") (name "Net-(U42-ADBUS2)") (class "Default")
      (node (ref "R265") (pin "1") (pinfunction "1_1") (pintype "passive"))
      (node (ref "U42") (pin "15") (pinfunction "ADBUS2_15") (pintype "bidirectional"))
    )
    (net (code "42") (name "Net-(U42-OSCI)") (class "Default")
      (node (ref "U42") (pin "1") (pinfunction "OSCI_1") (pintype "input"))
      (node (ref "U45") (pin "3") (pinfunction "OUT_3") (pintype "output"))
    )
    (net (code "43") (name "Net-(U42-REF)") (class "Default")
      (node (ref "R273") (pin "2") (pinfunction "2_2") (pintype "passive"))
      (node (ref "U42") (pin "5") (pinfunction "REF_5") (pintype "input"))
    )
    (net (code "44") (name "Net-(U42-VCCA)") (class "Default")
      (node (ref "C466") (pin "2") (pinfunction "2_2") (pintype "passive"))
      (node (ref "U42") (pin "37") (pinfunction "VCCA_37") (pintype "power_in"))
    )
    (net (code "45") (name "Net-(U42-VCORE)") (class "Default")
      (node (ref "C465") (pin "2") (pinfunction "2_2") (pintype "passive"))
      (node (ref "U42") (pin "38") (pinfunction "VCORE_38") (pintype "power_in"))
    )
    (net (code "46") (name "Net-(U46-D0)") (class "Default")
      (node (ref "R278") (pin "1") (pinfunction "1_1") (pintype "passive"))
      (node (ref "R281") (pin "1") (pinfunction "1_1") (pintype "passive"))
      (node (ref "U46") (pin "1") (pinfunction "D0_1") (pintype "output"))
    )
    (net (code "47") (name "Net-(U46-VSS)") (class "Default")
      (node (ref "C469") (pin "1") (pinfunction "1_1") (pintype "passive"))
      (node (ref "U46") (pin "2") (pinfunction "VSS_2") (pintype "power_in"))
    )
    (net (code "48") (name "Net-(U47-D+)") (class "Default")
      (node (ref "R284") (pin "1") (pinfunction "1_1") (pintype "passive"))
      (node (ref "U47") (pin "14") (pinfunction "D+_14") (pintype "bidirectional"))
    )
    (net (code "49") (name "Net-(U47-D)") (class "Default")
      (node (ref "R286") (pin "1") (pinfunction "1_1") (pintype "passive"))
      (node (ref "U47") (pin "15") (pinfunction "D_15") (pintype "bidirectional"))
    )
    (net (code "50") (name "Net-(U47-VBUS)") (class "Default")
      (node (ref "R285") (pin "1") (pinfunction "1_1") (pintype "passive"))
      (node (ref "U47") (pin "7") (pinfunction "VBUS_7") (pintype "input"))
    )
    (net (code "51") (name "SHIELD") (class "Default")
      (node (ref "J5") (pin "S1") (pinfunction "S1_S1") (pintype "power_in"))
      (node (ref "J5") (pin "S2") (pinfunction "S2_S2") (pintype "power_in"))
      (node (ref "J5") (pin "S3") (pinfunction "S3_S3") (pintype "power_in"))
      (node (ref "J5") (pin "S4") (pinfunction "S4_S4") (pintype "power_in"))
      (node (ref "J6") (pin "S1") (pinfunction "S1_S1") (pintype "power_in"))
      (node (ref "J6") (pin "S2") (pinfunction "S2_S2") (pintype "power_in"))
      (node (ref "J6") (pin "S3") (pinfunction "S3_S3") (pintype "power_in"))
      (node (ref "J6") (pin "S4") (pinfunction "S4_S4") (pintype "power_in"))
    )
    (net (code "52") (name "VCC1V8") (class "Default")
      (node (ref "C478") (pin "2") (pinfunction "2_2") (pintype "passive"))
      (node (ref "U43") (pin "5") (pinfunction "VCC_5") (pintype "passive"))
    )
    (net (code "53") (name "VCC3V3") (class "Default")
      (node (ref "C457") (pin "2") (pinfunction "2_2") (pintype "passive"))
      (node (ref "C458") (pin "2") (pinfunction "2_2") (pintype "passive"))
      (node (ref "C459") (pin "2") (pinfunction "2_2") (pintype "passive"))
      (node (ref "C460") (pin "2") (pinfunction "2_2") (pintype "passive"))
      (node (ref "C461") (pin "2") (pinfunction "2_2") (pintype "passive"))
      (node (ref "C462") (pin "2") (pinfunction "2_2") (pintype "passive"))
      (node (ref "C463") (pin "2") (pinfunction "2_2") (pintype "passive"))
      (node (ref "C464") (pin "2") (pinfunction "2_2") (pintype "passive"))
      (node (ref "C468") (pin "2") (pinfunction "2_2") (pintype "passive"))
      (node (ref "C469") (pin "2") (pinfunction "2_2") (pintype "passive"))
      (node (ref "C470") (pin "2") (pinfunction "2_2") (pintype "passive"))
      (node (ref "C471") (pin "2") (pinfunction "2_2") (pintype "passive"))
      (node (ref "D29") (pin "1") (pinfunction "K_1") (pintype "passive"))
      (node (ref "FB27") (pin "1") (pinfunction "1_1") (pintype "passive"))
      (node (ref "FB28") (pin "1") (pinfunction "1_1") (pintype "passive"))
      (node (ref "R261") (pin "2") (pinfunction "2_2") (pintype "passive"))
      (node (ref "R263") (pin "2") (pinfunction "2_2") (pintype "passive"))
      (node (ref "R267") (pin "2") (pinfunction "2_2") (pintype "passive"))
      (node (ref "R268") (pin "1") (pinfunction "1_1") (pintype "passive"))
      (node (ref "R271") (pin "2") (pinfunction "2_2") (pintype "passive"))
      (node (ref "R274") (pin "2") (pinfunction "2_2") (pintype "passive"))
      (node (ref "R275") (pin "2") (pinfunction "2_2") (pintype "passive"))
      (node (ref "R276") (pin "2") (pinfunction "2_2") (pintype "passive"))
      (node (ref "R277") (pin "2") (pinfunction "2_2") (pintype "passive"))
      (node (ref "R278") (pin "2") (pinfunction "2_2") (pintype "passive"))
      (node (ref "R279") (pin "2") (pinfunction "2_2") (pintype "passive"))
      (node (ref "R280") (pin "2") (pinfunction "2_2") (pintype "passive"))
      (node (ref "R282") (pin "1") (pinfunction "1_1") (pintype "passive"))
      (node (ref "U41") (pin "7") (pinfunction "GND_7") (pintype "passive"))
      (node (ref "U42") (pin "12") (pinfunction "VCCIO_12") (pintype "power_in"))
      (node (ref "U42") (pin "24") (pinfunction "VCCIO_24") (pintype "power_in"))
      (node (ref "U42") (pin "39") (pinfunction "VCCD_39") (pintype "power_in"))
      (node (ref "U42") (pin "40") (pinfunction "VREGIN_40") (pintype "power_in"))
      (node (ref "U42") (pin "46") (pinfunction "VCCIO_46") (pintype "power_in"))
      (node (ref "U44") (pin "6") (pinfunction "VCC_6") (pintype "passive"))
      (node (ref "U45") (pin "4") (pinfunction "VCC_4") (pintype "power_in"))
      (node (ref "U46") (pin "6") (pinfunction "VCC_6") (pintype "power_in"))
    )
    (net (code "54") (name "unconnected-(D30A-K-Pad1)") (class "Default")
      (node (ref "D30") (pin "1") (pinfunction "K_1") (pintype "passive+no_connect"))
    )
    (net (code "55") (name "unconnected-(D30D-K-Pad4)") (class "Default")
      (node (ref "D30") (pin "4") (pinfunction "K_4") (pintype "passive+no_connect"))
    )
    (net (code "56") (name "unconnected-(D31D-K-Pad4)") (class "Default")
      (node (ref "D31") (pin "4") (pinfunction "K_4") (pintype "passive+no_connect"))
    )
    (net (code "57") (name "unconnected-(J5-ID-Pad4)") (class "Default")
      (node (ref "J5") (pin "4") (pinfunction "ID_4") (pintype "bidirectional+no_connect"))
    )
    (net (code "58") (name "unconnected-(J5-V-Pad1)") (class "Default")
      (node (ref "J5") (pin "1") (pinfunction "V_1") (pintype "power_in+no_connect"))
    )
    (net (code "59") (name "unconnected-(J6-ID-Pad4)") (class "Default")
      (node (ref "J6") (pin "4") (pinfunction "ID_4") (pintype "bidirectional+no_connect"))
    )
    (net (code "60") (name "unconnected-(R283-Pad2)") (class "Default")
      (node (ref "R283") (pin "2") (pinfunction "2_2") (pintype "passive"))
    )
    (net (code "61") (name "unconnected-(U42-ACBUS0-Pad21)") (class "Default")
      (node (ref "U42") (pin "21") (pinfunction "ACBUS0_21") (pintype "bidirectional+no_connect"))
    )
    (net (code "62") (name "unconnected-(U42-ACBUS1-Pad25)") (class "Default")
      (node (ref "U42") (pin "25") (pinfunction "ACBUS1_25") (pintype "bidirectional+no_connect"))
    )
    (net (code "63") (name "unconnected-(U42-ACBUS2-Pad26)") (class "Default")
      (node (ref "U42") (pin "26") (pinfunction "ACBUS2_26") (pintype "bidirectional+no_connect"))
    )
    (net (code "64") (name "unconnected-(U42-ACBUS3-Pad27)") (class "Default")
      (node (ref "U42") (pin "27") (pinfunction "ACBUS3_27") (pintype "bidirectional+no_connect"))
    )
    (net (code "65") (name "unconnected-(U42-ACBUS6-Pad30)") (class "Default")
      (node (ref "U42") (pin "30") (pinfunction "ACBUS6_30") (pintype "bidirectional+no_connect"))
    )
    (net (code "66") (name "unconnected-(U42-ACBUS7-Pad31)") (class "Default")
      (node (ref "U42") (pin "31") (pinfunction "ACBUS7_31") (pintype "bidirectional+no_connect"))
    )
    (net (code "67") (name "unconnected-(U42-ACBUS8-Pad32)") (class "Default")
      (node (ref "U42") (pin "32") (pinfunction "ACBUS8_32") (pintype "bidirectional+no_connect"))
    )
    (net (code "68") (name "unconnected-(U42-ACBUS9-Pad33)") (class "Default")
      (node (ref "U42") (pin "33") (pinfunction "ACBUS9_33") (pintype "bidirectional+no_connect"))
    )
    (net (code "69") (name "unconnected-(U42-OSCO-Pad2)") (class "Default")
      (node (ref "U42") (pin "2") (pinfunction "OSCO_2") (pintype "output+no_connect"))
    )
    (net (code "70") (name "unconnected-(U44B-NC-Pad5)") (class "Default")
      (node (ref "U44") (pin "5") (pinfunction "NC_5") (pintype "passive+no_connect"))
    )
    (net (code "71") (name "unconnected-(U45-E_D-Pad1)") (class "Default")
      (node (ref "U45") (pin "1") (pinfunction "E_D_1") (pintype "input+no_connect"))
    )
    (net (code "72") (name "unconnected-(U47-DTR-Pad5)") (class "Default")
      (node (ref "U47") (pin "5") (pinfunction "DTR_5") (pintype "output+no_connect"))
    )
    (net (code "73") (name "unconnected-(U47-NC-Pad9)") (class "Default")
      (node (ref "U47") (pin "9") (pinfunction "NC_9") (pintype "passive+no_connect"))
    )
    (net (code "74") (name "unconnected-(U47-NC-Pad10)") (class "Default")
      (node (ref "U47") (pin "10") (pinfunction "NC_10") (pintype "passive+no_connect"))
    )
    (net (code "75") (name "unconnected-(U47-NC-Pad11)") (class "Default")
      (node (ref "U47") (pin "11") (pinfunction "NC_11") (pintype "passive+no_connect"))
    )
    (net (code "76") (name "unconnected-(U47-NC-Pad12)") (class "Default")
      (node (ref "U47") (pin "12") (pinfunction "NC_12") (pintype "passive+no_connect"))
    )
    (net (code "77") (name "unconnected-(U47-NC-Pad17)") (class "Default")
      (node (ref "U47") (pin "17") (pinfunction "NC_17") (pintype "passive+no_connect"))
    )
    (net (code "78") (name "unconnected-(U47-NC-Pad18)") (class "Default")
      (node (ref "U47") (pin "18") (pinfunction "NC_18") (pintype "passive+no_connect"))
    )
    (net (code "79") (name "unconnected-(U47-NC-Pad19)") (class "Default")
      (node (ref "U47") (pin "19") (pinfunction "NC_19") (pintype "passive+no_connect"))
    )
    (net (code "80") (name "unconnected-(U47-NC-Pad20)") (class "Default")
      (node (ref "U47") (pin "20") (pinfunction "NC_20") (pintype "passive+no_connect"))
    )
    (net (code "81") (name "unconnected-(U47-NC-Pad25)") (class "Default")
      (node (ref "U47") (pin "25") (pinfunction "NC_25") (pintype "passive+no_connect"))
    )
    (net (code "82") (name "unconnected-(U47-RTS-Pad24)") (class "Default")
      (node (ref "U47") (pin "24") (pinfunction "RTS_24") (pintype "output+no_connect"))
    )
    (net (code "83") (name "unconnected-(U47-Suspend-Pad3)") (class "Default")
      (node (ref "U47") (pin "3") (pinfunction "Suspend_3") (pintype "output+no_connect"))
    )
    (net (code "84") (name "unconnected-(U47-VCFG-Pad26)") (class "Default")
      (node (ref "U47") (pin "26") (pinfunction "VCFG_26") (pintype "output+no_connect"))
    )
  )
)
